# CalibradorDePlacas.net
KiCad netlist of a schematic drawn in Altium Designer
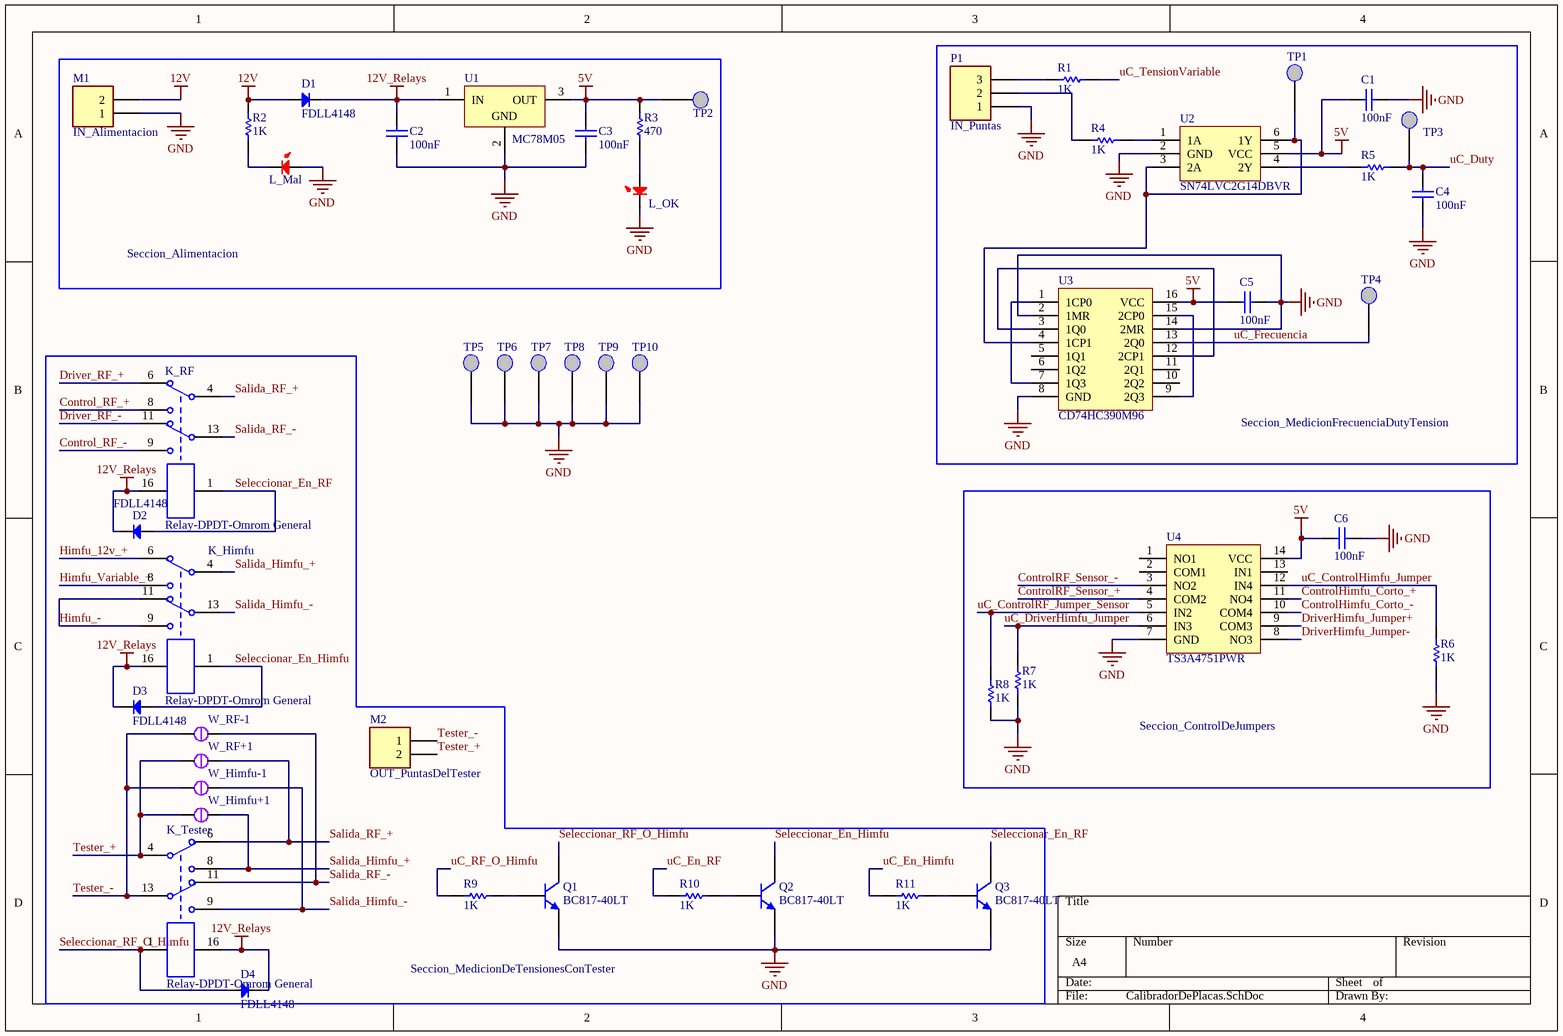
[diagram p0: CalibradorDePlacas.SchDoc]

(export (version "E")
  (design (tool "Eeschema 10.0.6"))
  (components
    (comp (ref "C1")
      (value "100nF")
      (footprint "Nahuel_SMD_Body:C_0805")
      (description "CAP CER 0.1UF 25V X7R 0805")
      (fields (field (name "PUBLISHER") "Altium Limited"))
      (libsource (lib "Nahuel_SMD_Body") (part "C_100nF"))
    )
    (comp (ref "C2")
      (value "100nF")
      (footprint "Nahuel_SMD_Body:C_0805")
      (description "CAP CER 0.1UF 25V X7R 0805")
      (fields (field (name "PUBLISHER") "Altium Limited"))
      (libsource (lib "Nahuel_SMD_Body") (part "C_100nF"))
    )
    (comp (ref "C3")
      (value "100nF")
      (footprint "Nahuel_SMD_Body:C_0805")
      (description "CAP CER 0.1UF 25V X7R 0805")
      (fields (field (name "PUBLISHER") "Altium Limited"))
      (libsource (lib "Nahuel_SMD_Body") (part "C_100nF"))
    )
    (comp (ref "C4")
      (value "100nF")
      (footprint "Nahuel_SMD_Body:C_0805")
      (description "CAP CER 0.1UF 25V X7R 0805")
      (fields (field (name "PUBLISHER") "Altium Limited"))
      (libsource (lib "Nahuel_SMD_Body") (part "C_100nF"))
    )
    (comp (ref "C5")
      (value "100nF")
      (footprint "Nahuel_SMD_Body:C_0805")
      (description "CAP CER 0.1UF 25V X7R 0805")
      (fields (field (name "PUBLISHER") "Altium Limited"))
      (libsource (lib "Nahuel_SMD_Body") (part "C_100nF"))
    )
    (comp (ref "C6")
      (value "100nF")
      (footprint "Nahuel_SMD_Body:C_0805")
      (description "CAP CER 0.1UF 25V X7R 0805")
      (fields (field (name "PUBLISHER") "Altium Limited"))
      (libsource (lib "Nahuel_SMD_Body") (part "C_100nF"))
    )
    (comp (ref "D1")
      (value "FDLL4148")
      (footprint "SOD-80/MLL34")
      (description "DIODE GEN PURP 100V 200MA LL34/SOD80/MINI MELF")
      (fields (field (name "PUBLISHER") "Altium Limited"))
      (libsource (lib "Nahuel_SMD_Body") (part "Diode FDLL4148"))
    )
    (comp (ref "D2")
      (value "FDLL4148")
      (footprint "SOD-80/MLL34")
      (description "DIODE GEN PURP 100V 200MA LL34/SOD80/MINI MELF")
      (fields (field (name "PUBLISHER") "Altium Limited"))
      (libsource (lib "Nahuel_SMD_Body") (part "Diode FDLL4148"))
    )
    (comp (ref "D3")
      (value "FDLL4148")
      (footprint "SOD-80/MLL34")
      (description "DIODE GEN PURP 100V 200MA LL34/SOD80/MINI MELF")
      (fields (field (name "PUBLISHER") "Altium Limited"))
      (libsource (lib "Nahuel_SMD_Body") (part "Diode FDLL4148"))
    )
    (comp (ref "D4")
      (value "FDLL4148")
      (footprint "SOD-80/MLL34")
      (description "DIODE GEN PURP 100V 200MA LL34/SOD80/MINI MELF")
      (fields (field (name "PUBLISHER") "Altium Limited"))
      (libsource (lib "Nahuel_SMD_Body") (part "Diode FDLL4148"))
    )
    (comp (ref "K_Himfu")
      (value "Relay-DPDT-Omrom General")
      (footprint "Nahuel_TH_BODY:RELAY_DPDT")
      (description "RELAY GEN PURPOSE DPDT 1A 12VDC")
      (fields (field (name "PUBLISHER") "Altium Limited"))
      (libsource (lib "Nahuel_TH_BODY") (part "Relay-DPDT-Omrom General"))
    )
    (comp (ref "K_RF")
      (value "Relay-DPDT-Omrom General")
      (footprint "Nahuel_TH_BODY:RELAY_DPDT")
      (description "RELAY GEN PURPOSE DPDT 1A 12VDC")
      (fields (field (name "PUBLISHER") "Altium Limited"))
      (libsource (lib "Nahuel_TH_BODY") (part "Relay-DPDT-Omrom General"))
    )
    (comp (ref "K_Tester")
      (value "Relay-DPDT-Omrom General")
      (footprint "Nahuel_TH_BODY:RELAY_DPDT")
      (description "RELAY GEN PURPOSE DPDT 1A 12VDC")
      (fields (field (name "PUBLISHER") "Altium Limited"))
      (libsource (lib "Nahuel_TH_BODY") (part "Relay-DPDT-Omrom General"))
    )
    (comp (ref "L_Mal")
      (value "PinesParaLed")
      (footprint "Nahuel_TH_BODY:Jumper-Simple")
      (description "CONN HEADER 2 POS 2.54")
      (fields (field (name "PUBLISHER") "Altium Limited"))
      (libsource (lib "Nahuel_TH_BODY") (part "PinesParaLed"))
    )
    (comp (ref "L_OK")
      (value "PinesParaLed")
      (footprint "Nahuel_TH_BODY:Jumper-Simple")
      (description "CONN HEADER 2 POS 2.54")
      (fields (field (name "PUBLISHER") "Altium Limited"))
      (libsource (lib "Nahuel_TH_BODY") (part "PinesParaLed"))
    )
    (comp (ref "M1")
      (value "IN_Alimentacion")
      (footprint "B2B-XH-A_3D")
      (description "CONN HEADER XH TOP 2POS 2.5MM")
      (fields (field (name "PUBLISHER") "Altium Limited"))
      (libsource (lib "Nahuel_Connectors_BODY") (part "JST_2.5_2"))
    )
    (comp (ref "M2")
      (value "OUT_PuntasDelTester")
      (footprint "B2B-XH-A_3D")
      (description "CONN HEADER XH TOP 2POS 2.5MM")
      (fields (field (name "PUBLISHER") "Altium Limited"))
      (libsource (lib "") (part "JST_2.5_2_1"))
    )
    (comp (ref "P1")
      (value "IN_Puntas")
      (footprint "B3B-XH-A_3D")
      (description "CONN HEADER XH TOP 3POS 2.5MM")
      (fields (field (name "PUBLISHER") "Altium Limited"))
      (libsource (lib "Nahuel_Connectors_BODY") (part "JST_2.5_3"))
    )
    (comp (ref "Q1")
      (value "BC817-40LT")
      (footprint "Nahuel_SMD_Body:SOT23")
      (description "TRANS NPN 45V 0.5A SOT23")
      (fields (field (name "PUBLISHER") "Altium Limited"))
      (libsource (lib "Nahuel_SMD_Body") (part "BC817"))
    )
    (comp (ref "Q2")
      (value "BC817-40LT")
      (footprint "Nahuel_SMD_Body:SOT23")
      (description "TRANS NPN 45V 0.5A SOT23")
      (fields (field (name "PUBLISHER") "Altium Limited"))
      (libsource (lib "Nahuel_SMD_Body") (part "BC817"))
    )
    (comp (ref "Q3")
      (value "BC817-40LT")
      (footprint "Nahuel_SMD_Body:SOT23")
      (description "TRANS NPN 45V 0.5A SOT23")
      (fields (field (name "PUBLISHER") "Altium Limited"))
      (libsource (lib "Nahuel_SMD_Body") (part "BC817"))
    )
    (comp (ref "R1")
      (value "1K")
      (footprint "Nahuel_SMD_Body:R_0805")
      (description "RES SMD 1K OHM 1% 1/8W 0805")
      (fields (field (name "PUBLISHER") "Altium Limited"))
      (libsource (lib "Nahuel_SMD_Body") (part "R_1k"))
    )
    (comp (ref "R2")
      (value "1K")
      (footprint "Nahuel_SMD_Body:R_0805")
      (description "RES SMD 1K OHM 1% 1/8W 0805")
      (fields (field (name "PUBLISHER") "Altium Limited"))
      (libsource (lib "Nahuel_SMD_Body") (part "R_1k"))
    )
    (comp (ref "R3")
      (value "470")
      (footprint "Nahuel_SMD_Body:R_0805")
      (description "RES SMD 470 OHM 1% 1/8W 0805")
      (fields (field (name "PUBLISHER") "Altium Limited"))
      (libsource (lib "Nahuel_SMD_Body") (part "R_470"))
    )
    (comp (ref "R4")
      (value "1K")
      (footprint "Nahuel_SMD_Body:R_0805")
      (description "RES SMD 1K OHM 1% 1/8W 0805")
      (fields (field (name "PUBLISHER") "Altium Limited"))
      (libsource (lib "Nahuel_SMD_Body") (part "R_1k"))
    )
    (comp (ref "R5")
      (value "1K")
      (footprint "Nahuel_SMD_Body:R_0805")
      (description "RES SMD 1K OHM 1% 1/8W 0805")
      (fields (field (name "PUBLISHER") "Altium Limited"))
      (libsource (lib "Nahuel_SMD_Body") (part "R_1k"))
    )
    (comp (ref "R6")
      (value "1K")
      (footprint "Nahuel_SMD_Body:R_0805")
      (description "RES SMD 1K OHM 1% 1/8W 0805")
      (fields (field (name "PUBLISHER") "Altium Limited"))
      (libsource (lib "Nahuel_SMD_Body") (part "R_1k"))
    )
    (comp (ref "R7")
      (value "1K")
      (footprint "Nahuel_SMD_Body:R_0805")
      (description "RES SMD 1K OHM 1% 1/8W 0805")
      (fields (field (name "PUBLISHER") "Altium Limited"))
      (libsource (lib "Nahuel_SMD_Body") (part "R_1k"))
    )
    (comp (ref "R8")
      (value "1K")
      (footprint "Nahuel_SMD_Body:R_0805")
      (description "RES SMD 1K OHM 1% 1/8W 0805")
      (fields (field (name "PUBLISHER") "Altium Limited"))
      (libsource (lib "Nahuel_SMD_Body") (part "R_1k"))
    )
    (comp (ref "R9")
      (value "1K")
      (footprint "Nahuel_SMD_Body:R_0805")
      (description "RES SMD 1K OHM 1% 1/8W 0805")
      (fields (field (name "PUBLISHER") "Altium Limited"))
      (libsource (lib "Nahuel_SMD_Body") (part "R_1k"))
    )
    (comp (ref "R10")
      (value "1K")
      (footprint "Nahuel_SMD_Body:R_0805")
      (description "RES SMD 1K OHM 1% 1/8W 0805")
      (fields (field (name "PUBLISHER") "Altium Limited"))
      (libsource (lib "Nahuel_SMD_Body") (part "R_1k"))
    )
    (comp (ref "R11")
      (value "1K")
      (footprint "Nahuel_SMD_Body:R_0805")
      (description "RES SMD 1K OHM 1% 1/8W 0805")
      (fields (field (name "PUBLISHER") "Altium Limited"))
      (libsource (lib "Nahuel_SMD_Body") (part "R_1k"))
    )
    (comp (ref "TP1")
      (value "IN_F")
      (footprint "Nahuel_TH_BODY:TP-5002")
      (fields (field (name "PUBLISHER") "Altium Limited"))
      (libsource (lib "") (part "TestPoint_1"))
    )
    (comp (ref "TP2")
      (value "5V")
      (footprint "Nahuel_TH_BODY:TP-5002")
      (fields (field (name "PUBLISHER") "Altium Limited"))
      (libsource (lib "Nahuel_TH_BODY") (part "TestPoint"))
    )
    (comp (ref "TP3")
      (value "OUT_D")
      (footprint "Nahuel_TH_BODY:TP-5002")
      (fields (field (name "PUBLISHER") "Altium Limited"))
      (libsource (lib "") (part "TestPoint_1"))
    )
    (comp (ref "TP4")
      (value "OUT_F")
      (footprint "Nahuel_TH_BODY:TP-5002")
      (fields (field (name "PUBLISHER") "Altium Limited"))
      (libsource (lib "") (part "TestPoint_1"))
    )
    (comp (ref "TP5")
      (value "GND")
      (footprint "Nahuel_TH_BODY:TP-5002")
      (fields (field (name "PUBLISHER") "Altium Limited"))
      (libsource (lib "") (part "TestPoint_1"))
    )
    (comp (ref "TP6")
      (value "GND")
      (footprint "Nahuel_TH_BODY:TP-5002")
      (fields (field (name "PUBLISHER") "Altium Limited"))
      (libsource (lib "") (part "TestPoint_1"))
    )
    (comp (ref "TP7")
      (value "GND")
      (footprint "Nahuel_TH_BODY:TP-5002")
      (fields (field (name "PUBLISHER") "Altium Limited"))
      (libsource (lib "") (part "TestPoint_1"))
    )
    (comp (ref "TP8")
      (value "GND")
      (footprint "Nahuel_TH_BODY:TP-5002")
      (fields (field (name "PUBLISHER") "Altium Limited"))
      (libsource (lib "") (part "TestPoint_1"))
    )
    (comp (ref "TP9")
      (value "GND")
      (footprint "Nahuel_TH_BODY:TP-5002")
      (fields (field (name "PUBLISHER") "Altium Limited"))
      (libsource (lib "") (part "TestPoint_1"))
    )
    (comp (ref "TP10")
      (value "GND")
      (footprint "Nahuel_TH_BODY:TP-5002")
      (fields (field (name "PUBLISHER") "Altium Limited"))
      (libsource (lib "") (part "TestPoint_1"))
    )
    (comp (ref "U1")
      (value "MC78M05")
      (footprint "TO-252AA_N")
      (description "IC REG LINEAR 5V 500MA DPAK")
      (fields (field (name "PUBLISHER") "Altium Limited"))
      (libsource (lib "Nahuel_SMD_Body") (part "MC78M05"))
    )
    (comp (ref "U2")
      (value "SN74LVC2G14DBVR")
      (footprint "Nahuel_SMD_Body:SOT23-6")
      (description "IC INVERTER SCHMITT 2CH SOT23-6")
      (fields (field (name "PUBLISHER") "Altium Limited"))
      (libsource (lib "Nahuel_SMD_Body") (part "SN74LVC2G14DBVR"))
    )
    (comp (ref "U3")
      (value "CD74HC390M96")
      (footprint "Nahuel_SMD_Body:SOIC16")
      (description "IC DUAL DECADE RPL COUNTR 16SOIC")
      (fields (field (name "PUBLISHER") "Altium Limited"))
      (libsource (lib "Nahuel_SMD_Body") (part "CD74HC390M96"))
    )
    (comp (ref "U4")
      (value "TS3A4751PWR")
      (footprint "Nahuel_SMD_Body:TSSOP14")
      (description "IC SWITCH QUAD SPST 14TSSOP")
      (fields (field (name "PUBLISHER") "Altium Limited"))
      (libsource (lib "Nahuel_SMD_Body") (part "TS3A4751PWR"))
    )
    (comp (ref "W_Himfu+1")
      (value "JMP")
      (footprint "Nahuel_SMD_Body:SMD_JMP")
      (description "Islas para hacer un jumper con estaño")
      (libsource (lib "Nahuel_SMD_Body") (part "SMD_JMP"))
    )
    (comp (ref "W_Himfu-1")
      (value "JMP")
      (footprint "Nahuel_SMD_Body:SMD_JMP")
      (description "Islas para hacer un jumper con estaño")
      (libsource (lib "Nahuel_SMD_Body") (part "SMD_JMP"))
    )
    (comp (ref "W_RF+1")
      (value "JMP")
      (footprint "Nahuel_SMD_Body:SMD_JMP")
      (description "Islas para hacer un jumper con estaño")
      (libsource (lib "Nahuel_SMD_Body") (part "SMD_JMP"))
    )
    (comp (ref "W_RF-1")
      (value "JMP")
      (footprint "Nahuel_SMD_Body:SMD_JMP")
      (description "Islas para hacer un jumper con estaño")
      (libsource (lib "Nahuel_SMD_Body") (part "SMD_JMP"))
    )
  )
  (nets
    (net (code "1") (name "/ControlHimfu_Corto_+") (class "Default")
      (node (ref "U4") (pin "11") (pinfunction "NO4_11") (pintype "passive"))
    )
    (net (code "2") (name "/ControlHimfu_Corto_-") (class "Default")
      (node (ref "U4") (pin "10") (pinfunction "COM4_10") (pintype "passive"))
    )
    (net (code "3") (name "/ControlRF_Sensor_+") (class "Default")
      (node (ref "U4") (pin "4") (pinfunction "COM2_4") (pintype "passive"))
    )
    (net (code "4") (name "/ControlRF_Sensor_-") (class "Default")
      (node (ref "U4") (pin "3") (pinfunction "NO2_3") (pintype "passive"))
    )
    (net (code "5") (name "/Control_RF_+") (class "Default")
      (node (ref "K_RF") (pin "8") (pinfunction "NOb_8") (pintype "passive"))
    )
    (net (code "6") (name "/Control_RF_-") (class "Default")
      (node (ref "K_RF") (pin "9") (pinfunction "NOa_9") (pintype "passive"))
    )
    (net (code "7") (name "/DriverHimfu_Jumper+") (class "Default")
      (node (ref "U4") (pin "9") (pinfunction "COM3_9") (pintype "passive"))
    )
    (net (code "8") (name "/DriverHimfu_Jumper-") (class "Default")
      (node (ref "U4") (pin "8") (pinfunction "NO3_8") (pintype "passive"))
    )
    (net (code "9") (name "/Driver_RF_+") (class "Default")
      (node (ref "K_RF") (pin "6") (pinfunction "NCb_6") (pintype "passive"))
    )
    (net (code "10") (name "/Driver_RF_-") (class "Default")
      (node (ref "K_RF") (pin "11") (pinfunction "NCa_11") (pintype "passive"))
    )
    (net (code "11") (name "/Himfu_-") (class "Default")
      (node (ref "K_Himfu") (pin "11") (pinfunction "NCa_11") (pintype "passive"))
      (node (ref "K_Himfu") (pin "9") (pinfunction "NOa_9") (pintype "passive"))
    )
    (net (code "12") (name "/Himfu_12v_+") (class "Default")
      (node (ref "K_Himfu") (pin "6") (pinfunction "NCb_6") (pintype "passive"))
    )
    (net (code "13") (name "/Himfu_Variable_+") (class "Default")
      (node (ref "K_Himfu") (pin "8") (pinfunction "NOb_8") (pintype "passive"))
    )
    (net (code "14") (name "/Salida_Himfu_+") (class "Default")
      (node (ref "K_Himfu") (pin "4") (pinfunction "Cb_4") (pintype "passive"))
      (node (ref "K_Tester") (pin "8") (pinfunction "NOb_8") (pintype "passive"))
      (node (ref "W_Himfu+1") (pin "2") (pinfunction "2_2") (pintype "passive"))
    )
    (net (code "15") (name "/Salida_Himfu_-") (class "Default")
      (node (ref "K_Himfu") (pin "13") (pinfunction "Ca_13") (pintype "passive"))
      (node (ref "K_Tester") (pin "9") (pinfunction "NOa_9") (pintype "passive"))
      (node (ref "W_Himfu-1") (pin "2") (pinfunction "2_2") (pintype "passive"))
    )
    (net (code "16") (name "/Salida_RF_+") (class "Default")
      (node (ref "K_RF") (pin "4") (pinfunction "Cb_4") (pintype "passive"))
      (node (ref "K_Tester") (pin "6") (pinfunction "NCb_6") (pintype "passive"))
      (node (ref "W_RF+1") (pin "2") (pinfunction "2_2") (pintype "passive"))
    )
    (net (code "17") (name "/Salida_RF_-") (class "Default")
      (node (ref "K_RF") (pin "13") (pinfunction "Ca_13") (pintype "passive"))
      (node (ref "K_Tester") (pin "11") (pinfunction "NCa_11") (pintype "passive"))
      (node (ref "W_RF-1") (pin "2") (pinfunction "2_2") (pintype "passive"))
    )
    (net (code "18") (name "/Seleccionar_En_Himfu") (class "Default")
      (node (ref "D3") (pin "1") (pinfunction "A_1") (pintype "passive"))
      (node (ref "K_Himfu") (pin "1") (pinfunction "+_1") (pintype "passive"))
      (node (ref "Q2") (pin "3") (pinfunction "C_3") (pintype "passive"))
    )
    (net (code "19") (name "/Seleccionar_En_RF") (class "Default")
      (node (ref "D2") (pin "1") (pinfunction "A_1") (pintype "passive"))
      (node (ref "K_RF") (pin "1") (pinfunction "+_1") (pintype "passive"))
      (node (ref "Q3") (pin "3") (pinfunction "C_3") (pintype "passive"))
    )
    (net (code "20") (name "/Seleccionar_RF_O_Himfu") (class "Default")
      (node (ref "D4") (pin "1") (pinfunction "A_1") (pintype "passive"))
      (node (ref "K_Tester") (pin "1") (pinfunction "+_1") (pintype "passive"))
      (node (ref "Q1") (pin "3") (pinfunction "C_3") (pintype "passive"))
    )
    (net (code "21") (name "/Tester_+") (class "Default")
      (node (ref "K_Tester") (pin "4") (pinfunction "Cb_4") (pintype "passive"))
      (node (ref "M2") (pin "2") (pinfunction "2_2") (pintype "passive"))
      (node (ref "W_Himfu+1") (pin "1") (pinfunction "1_1") (pintype "passive"))
      (node (ref "W_RF+1") (pin "1") (pinfunction "1_1") (pintype "passive"))
    )
    (net (code "22") (name "/Tester_-") (class "Default")
      (node (ref "K_Tester") (pin "13") (pinfunction "Ca_13") (pintype "passive"))
      (node (ref "M2") (pin "1") (pinfunction "1_1") (pintype "passive"))
      (node (ref "W_Himfu-1") (pin "1") (pinfunction "1_1") (pintype "passive"))
      (node (ref "W_RF-1") (pin "1") (pinfunction "1_1") (pintype "passive"))
    )
    (net (code "23") (name "/uC_ControlHimfu_Jumper") (class "Default")
      (node (ref "R6") (pin "2") (pinfunction "2_2") (pintype "passive"))
      (node (ref "U4") (pin "12") (pinfunction "IN4_12") (pintype "passive"))
    )
    (net (code "24") (name "/uC_ControlRF_Jumper_Sensor") (class "Default")
      (node (ref "R8") (pin "2") (pinfunction "2_2") (pintype "passive"))
      (node (ref "U4") (pin "5") (pinfunction "IN2_5") (pintype "passive"))
    )
    (net (code "25") (name "/uC_DriverHimfu_Jumper") (class "Default")
      (node (ref "R7") (pin "2") (pinfunction "2_2") (pintype "passive"))
      (node (ref "U4") (pin "6") (pinfunction "IN3_6") (pintype "passive"))
    )
    (net (code "26") (name "/uC_Duty") (class "Default")
      (node (ref "C4") (pin "2") (pinfunction "2_2") (pintype "passive"))
      (node (ref "R5") (pin "2") (pinfunction "2_2") (pintype "passive"))
      (node (ref "TP3") (pin "1") (pinfunction "1_1") (pintype "passive"))
    )
    (net (code "27") (name "/uC_En_Himfu") (class "Default")
      (node (ref "R11") (pin "1") (pinfunction "1_1") (pintype "passive"))
    )
    (net (code "28") (name "/uC_En_RF") (class "Default")
      (node (ref "R10") (pin "1") (pinfunction "1_1") (pintype "passive"))
    )
    (net (code "29") (name "/uC_Frecuencia") (class "Default")
      (node (ref "TP4") (pin "1") (pinfunction "1_1") (pintype "passive"))
      (node (ref "U3") (pin "13") (pinfunction "2Q0_13") (pintype "passive"))
    )
    (net (code "30") (name "/uC_RF_O_Himfu") (class "Default")
      (node (ref "R9") (pin "1") (pinfunction "1_1") (pintype "passive"))
    )
    (net (code "31") (name "/uC_TensionVariable") (class "Default")
      (node (ref "R1") (pin "2") (pinfunction "2_2") (pintype "passive"))
    )
    (net (code "32") (name "5V") (class "Default")
      (node (ref "C1") (pin "1") (pinfunction "1_1") (pintype "passive"))
      (node (ref "C3") (pin "2") (pinfunction "2_2") (pintype "passive"))
      (node (ref "C5") (pin "1") (pinfunction "1_1") (pintype "passive"))
      (node (ref "C6") (pin "1") (pinfunction "1_1") (pintype "passive"))
      (node (ref "R3") (pin "2") (pinfunction "2_2") (pintype "passive"))
      (node (ref "TP2") (pin "1") (pinfunction "1_1") (pintype "passive"))
      (node (ref "U1") (pin "3") (pinfunction "OUT_3") (pintype "power_in"))
      (node (ref "U2") (pin "5") (pinfunction "VCC_5") (pintype "passive"))
      (node (ref "U3") (pin "16") (pinfunction "VCC_16") (pintype "passive"))
      (node (ref "U4") (pin "14") (pinfunction "VCC_14") (pintype "passive"))
    )
    (net (code "33") (name "12V") (class "Default")
      (node (ref "D1") (pin "1") (pinfunction "A_1") (pintype "passive"))
      (node (ref "M1") (pin "2") (pinfunction "2_2") (pintype "passive"))
      (node (ref "R2") (pin "2") (pinfunction "2_2") (pintype "passive"))
    )
    (net (code "34") (name "12V_Relays") (class "Default")
      (node (ref "C2") (pin "2") (pinfunction "2_2") (pintype "passive"))
      (node (ref "D1") (pin "2") (pinfunction "K_2") (pintype "passive"))
      (node (ref "D2") (pin "2") (pinfunction "K_2") (pintype "passive"))
      (node (ref "D3") (pin "2") (pinfunction "K_2") (pintype "passive"))
      (node (ref "D4") (pin "2") (pinfunction "K_2") (pintype "passive"))
      (node (ref "K_Himfu") (pin "16") (pinfunction "-_16") (pintype "passive"))
      (node (ref "K_RF") (pin "16") (pinfunction "-_16") (pintype "passive"))
      (node (ref "K_Tester") (pin "16") (pinfunction "-_16") (pintype "passive"))
      (node (ref "U1") (pin "1") (pinfunction "IN_1") (pintype "power_in"))
    )
    (net (code "35") (name "GND") (class "Default")
      (node (ref "C1") (pin "2") (pinfunction "2_2") (pintype "passive"))
      (node (ref "C2") (pin "1") (pinfunction "1_1") (pintype "passive"))
      (node (ref "C3") (pin "1") (pinfunction "1_1") (pintype "passive"))
      (node (ref "C4") (pin "1") (pinfunction "1_1") (pintype "passive"))
      (node (ref "C5") (pin "2") (pinfunction "2_2") (pintype "passive"))
      (node (ref "C6") (pin "2") (pinfunction "2_2") (pintype "passive"))
      (node (ref "L_Mal") (pin "1") (pinfunction "1_1") (pintype "passive"))
      (node (ref "L_OK") (pin "2") (pinfunction "2_2") (pintype "passive"))
      (node (ref "M1") (pin "1") (pinfunction "1_1") (pintype "passive"))
      (node (ref "P1") (pin "1") (pinfunction "1_1") (pintype "passive"))
      (node (ref "Q1") (pin "2") (pinfunction "E_2") (pintype "passive"))
      (node (ref "Q2") (pin "2") (pinfunction "E_2") (pintype "passive"))
      (node (ref "Q3") (pin "2") (pinfunction "E_2") (pintype "passive"))
      (node (ref "R6") (pin "1") (pinfunction "1_1") (pintype "passive"))
      (node (ref "R7") (pin "1") (pinfunction "1_1") (pintype "passive"))
      (node (ref "R8") (pin "1") (pinfunction "1_1") (pintype "passive"))
      (node (ref "TP10") (pin "1") (pinfunction "1_1") (pintype "passive"))
      (node (ref "TP5") (pin "1") (pinfunction "1_1") (pintype "passive"))
      (node (ref "TP6") (pin "1") (pinfunction "1_1") (pintype "passive"))
      (node (ref "TP7") (pin "1") (pinfunction "1_1") (pintype "passive"))
      (node (ref "TP8") (pin "1") (pinfunction "1_1") (pintype "passive"))
      (node (ref "TP9") (pin "1") (pinfunction "1_1") (pintype "passive"))
      (node (ref "U1") (pin "2") (pinfunction "GND_2") (pintype "power_in"))
      (node (ref "U2") (pin "2") (pinfunction "GND_2") (pintype "passive"))
      (node (ref "U3") (pin "14") (pinfunction "2MR_14") (pintype "passive"))
      (node (ref "U3") (pin "2") (pinfunction "1MR_2") (pintype "passive"))
      (node (ref "U3") (pin "8") (pinfunction "GND_8") (pintype "passive"))
      (node (ref "U4") (pin "7") (pinfunction "GND_7") (pintype "passive"))
    )
    (net (code "36") (name "Net-(L_Mal-Pad2)") (class "Default")
      (node (ref "L_Mal") (pin "2") (pinfunction "2_2") (pintype "passive"))
      (node (ref "R2") (pin "1") (pinfunction "1_1") (pintype "passive"))
    )
    (net (code "37") (name "Net-(L_OK-Pad1)") (class "Default")
      (node (ref "L_OK") (pin "1") (pinfunction "1_1") (pintype "passive"))
      (node (ref "R3") (pin "1") (pinfunction "1_1") (pintype "passive"))
    )
    (net (code "38") (name "Net-(P1-Pad2)") (class "Default")
      (node (ref "P1") (pin "2") (pinfunction "2_2") (pintype "passive"))
      (node (ref "R4") (pin "1") (pinfunction "1_1") (pintype "passive"))
    )
    (net (code "39") (name "Net-(P1-Pad3)") (class "Default")
      (node (ref "P1") (pin "3") (pinfunction "3_3") (pintype "passive"))
      (node (ref "R1") (pin "1") (pinfunction "1_1") (pintype "passive"))
    )
    (net (code "40") (name "Net-(Q1-B)") (class "Default")
      (node (ref "Q1") (pin "1") (pinfunction "B_1") (pintype "passive"))
      (node (ref "R9") (pin "2") (pinfunction "2_2") (pintype "passive"))
    )
    (net (code "41") (name "Net-(Q2-B)") (class "Default")
      (node (ref "Q2") (pin "1") (pinfunction "B_1") (pintype "passive"))
      (node (ref "R10") (pin "2") (pinfunction "2_2") (pintype "passive"))
    )
    (net (code "42") (name "Net-(Q3-B)") (class "Default")
      (node (ref "Q3") (pin "1") (pinfunction "B_1") (pintype "passive"))
      (node (ref "R11") (pin "2") (pinfunction "2_2") (pintype "passive"))
    )
    (net (code "43") (name "Net-(U2-1A)") (class "Default")
      (node (ref "R4") (pin "2") (pinfunction "2_2") (pintype "passive"))
      (node (ref "U2") (pin "1") (pinfunction "1A_1") (pintype "passive"))
    )
    (net (code "44") (name "Net-(U2-1Y)") (class "Default")
      (node (ref "TP1") (pin "1") (pinfunction "1_1") (pintype "passive"))
      (node (ref "U2") (pin "3") (pinfunction "2A_3") (pintype "passive"))
      (node (ref "U2") (pin "6") (pinfunction "1Y_6") (pintype "passive"))
      (node (ref "U3") (pin "4") (pinfunction "1CP1_4") (pintype "passive"))
    )
    (net (code "45") (name "Net-(U2-2Y)") (class "Default")
      (node (ref "R5") (pin "1") (pinfunction "1_1") (pintype "passive"))
      (node (ref "U2") (pin "4") (pinfunction "2Y_4") (pintype "passive"))
    )
    (net (code "46") (name "Net-(U3-1CP0)") (class "Default")
      (node (ref "U3") (pin "1") (pinfunction "1CP0_1") (pintype "passive"))
      (node (ref "U3") (pin "7") (pinfunction "1Q3_7") (pintype "passive"))
    )
    (net (code "47") (name "Net-(U3-1Q0)") (class "Default")
      (node (ref "U3") (pin "12") (pinfunction "2CP1_12") (pintype "passive"))
      (node (ref "U3") (pin "3") (pinfunction "1Q0_3") (pintype "passive"))
    )
    (net (code "48") (name "Net-(U3-2CP0)") (class "Default")
      (node (ref "U3") (pin "15") (pinfunction "2CP0_15") (pintype "passive"))
      (node (ref "U3") (pin "9") (pinfunction "2Q3_9") (pintype "passive"))
    )
    (net (code "49") (name "unconnected-(U3-1Q1-Pad5)") (class "Default")
      (node (ref "U3") (pin "5") (pinfunction "1Q1_5") (pintype "passive"))
    )
    (net (code "50") (name "unconnected-(U3-1Q2-Pad6)") (class "Default")
      (node (ref "U3") (pin "6") (pinfunction "1Q2_6") (pintype "passive"))
    )
    (net (code "51") (name "unconnected-(U3-2Q1-Pad11)") (class "Default")
      (node (ref "U3") (pin "11") (pinfunction "2Q1_11") (pintype "passive"))
    )
    (net (code "52") (name "unconnected-(U3-2Q2-Pad10)") (class "Default")
      (node (ref "U3") (pin "10") (pinfunction "2Q2_10") (pintype "passive"))
    )
    (net (code "53") (name "unconnected-(U4-COM1-Pad2)") (class "Default")
      (node (ref "U4") (pin "2") (pinfunction "COM1_2") (pintype "passive"))
    )
    (net (code "54") (name "unconnected-(U4-IN1-Pad13)") (class "Default")
      (node (ref "U4") (pin "13") (pinfunction "IN1_13") (pintype "passive"))
    )
    (net (code "55") (name "unconnected-(U4-NO1-Pad1)") (class "Default")
      (node (ref "U4") (pin "1") (pinfunction "NO1_1") (pintype "passive"))
    )
  )
)
